# 5-Band_50W_PA_50W_PA_OCP.net
KiCad netlist of a schematic drawn in EAGLE
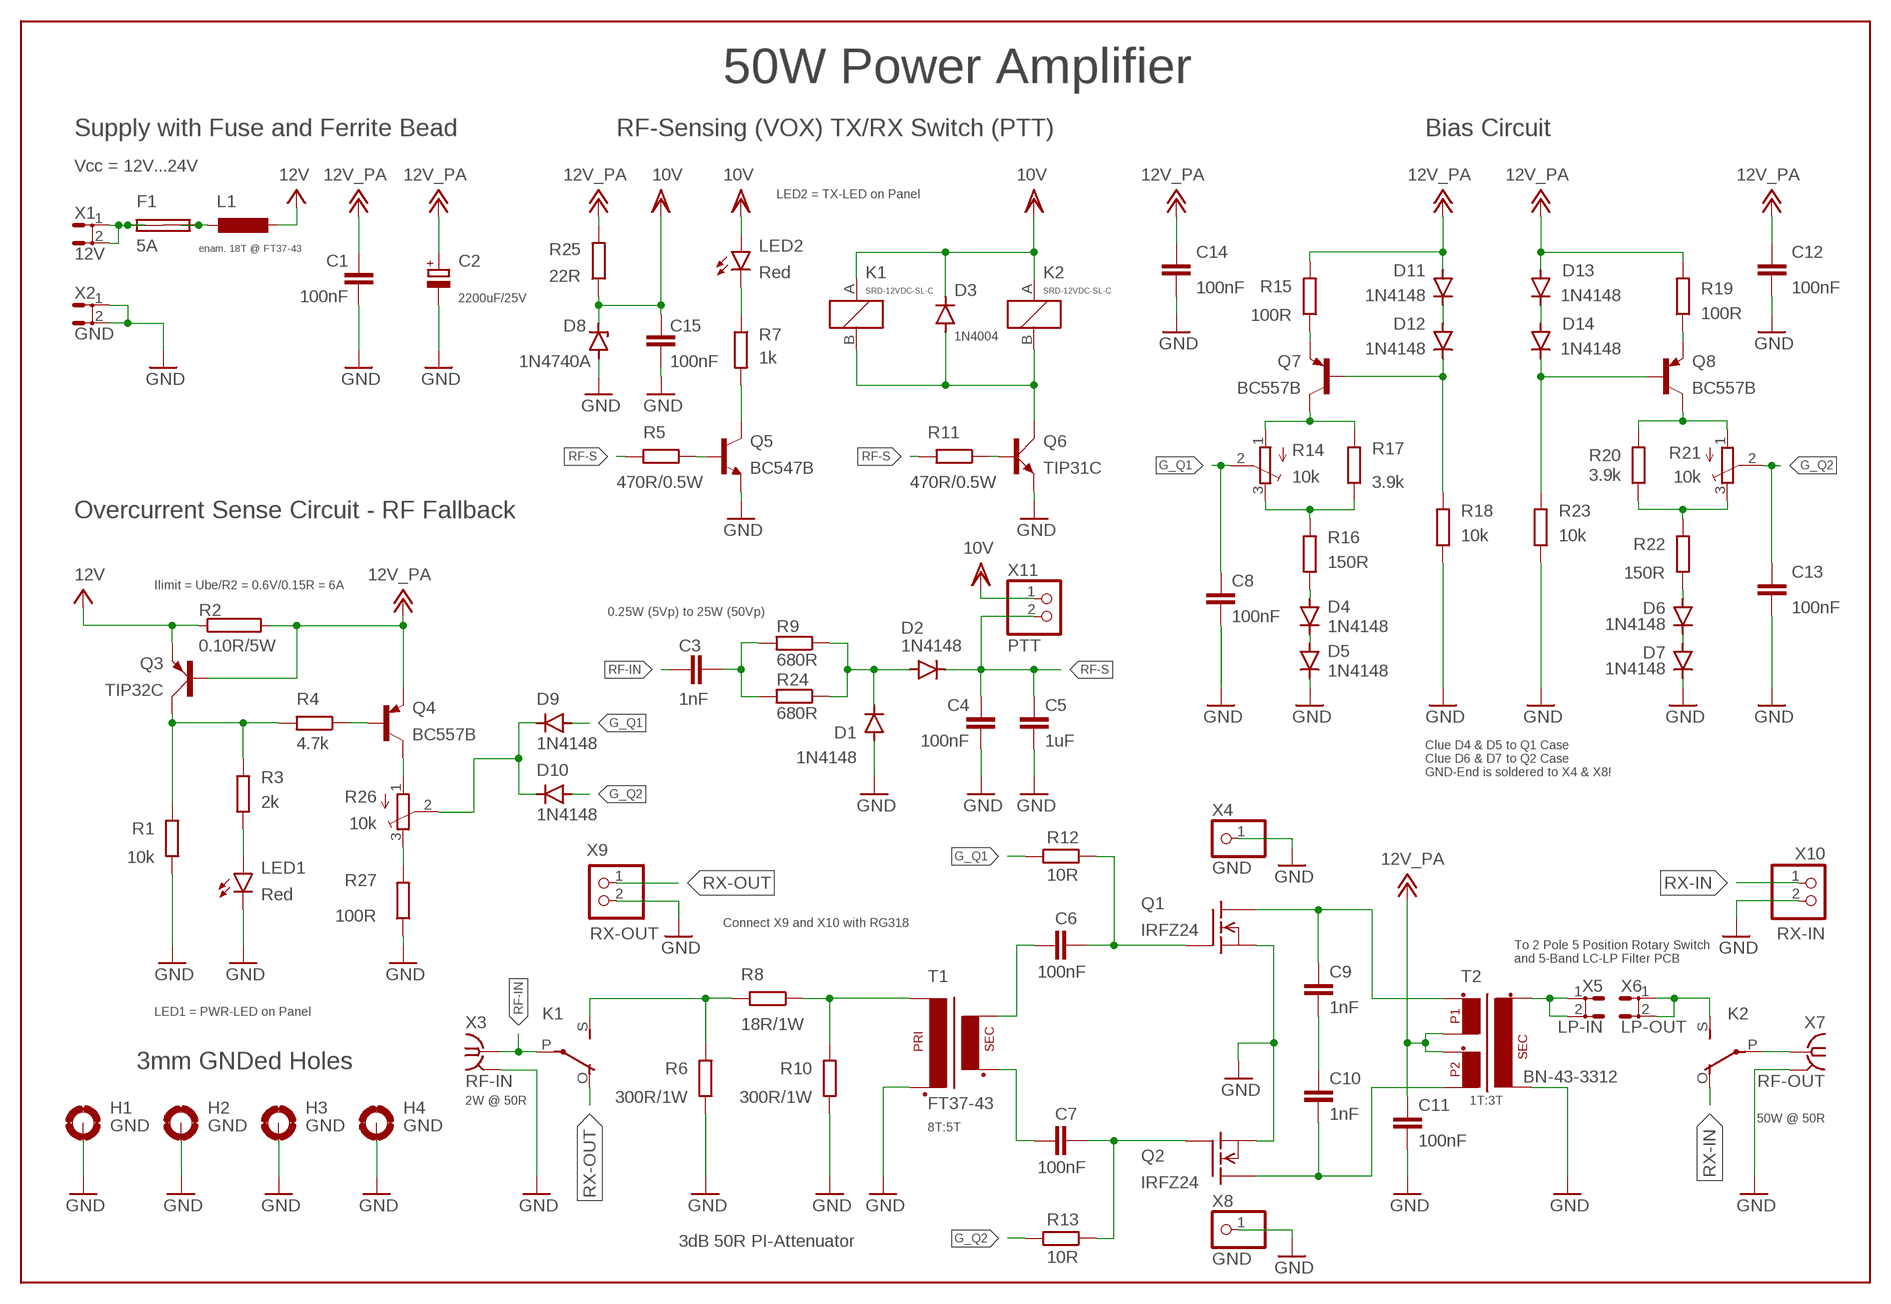
[diagram p0: schematic, sheet 1]

(export (version "E")
  (design (tool "Eeschema 10.0.6"))
  (components
    (comp (ref "C1")
      (value "100nF")
      (footprint "eagle-import:C0805")
      (libsource (lib "eagle-import") (part "C-EUC0805"))
    )
    (comp (ref "C2")
      (value "2200uF/25V")
      (footprint "eagle-import:E7,5-16")
      (libsource (lib "eagle-import") (part "CPOL-EUE7.5-16"))
    )
    (comp (ref "C3")
      (value "1nF")
      (footprint "eagle-import:C0805")
      (libsource (lib "eagle-import") (part "C-EUC0805"))
    )
    (comp (ref "C4")
      (value "100nF")
      (footprint "eagle-import:C0805")
      (libsource (lib "eagle-import") (part "C-EUC0805"))
    )
    (comp (ref "C5")
      (value "1uF")
      (footprint "eagle-import:C0805")
      (libsource (lib "eagle-import") (part "C-EUC0805"))
    )
    (comp (ref "C6")
      (value "100nF")
      (footprint "eagle-import:C0805")
      (libsource (lib "eagle-import") (part "C-EUC0805"))
    )
    (comp (ref "C7")
      (value "100nF")
      (footprint "eagle-import:C0805")
      (libsource (lib "eagle-import") (part "C-EUC0805"))
    )
    (comp (ref "C8")
      (value "100nF")
      (footprint "eagle-import:C0805")
      (libsource (lib "eagle-import") (part "C-EUC0805"))
    )
    (comp (ref "C9")
      (value "1nF")
      (footprint "eagle-import:C1206K")
      (libsource (lib "eagle-import") (part "C-EUC1206K"))
    )
    (comp (ref "C10")
      (value "1nF")
      (footprint "eagle-import:C1206K")
      (libsource (lib "eagle-import") (part "C-EUC1206K"))
    )
    (comp (ref "C11")
      (value "100nF")
      (footprint "eagle-import:C0805")
      (libsource (lib "eagle-import") (part "C-EUC0805"))
    )
    (comp (ref "C12")
      (value "100nF")
      (footprint "eagle-import:C0805")
      (libsource (lib "eagle-import") (part "C-EUC0805"))
    )
    (comp (ref "C13")
      (value "100nF")
      (footprint "eagle-import:C0805")
      (libsource (lib "eagle-import") (part "C-EUC0805"))
    )
    (comp (ref "C14")
      (value "100nF")
      (footprint "eagle-import:C0805")
      (libsource (lib "eagle-import") (part "C-EUC0805"))
    )
    (comp (ref "C15")
      (value "100nF")
      (footprint "eagle-import:C0805")
      (libsource (lib "eagle-import") (part "C-EUC0805"))
    )
    (comp (ref "D1")
      (value "1N4148")
      (footprint "eagle-import:SOD323-W")
      (libsource (lib "eagle-import") (part "DIODE-SOD323-W"))
    )
    (comp (ref "D2")
      (value "1N4148")
      (footprint "eagle-import:SOD323-W")
      (libsource (lib "eagle-import") (part "DIODE-SOD323-W"))
    )
    (comp (ref "D3")
      (value "1N4004")
      (footprint "eagle-import:DO41-10")
      (libsource (lib "eagle-import") (part "1N4004"))
    )
    (comp (ref "D4")
      (value "1N4148")
      (footprint "eagle-import:DO35-7")
      (libsource (lib "eagle-import") (part "1N4148DO35-7"))
    )
    (comp (ref "D5")
      (value "1N4148")
      (footprint "eagle-import:DO35-7")
      (libsource (lib "eagle-import") (part "1N4148DO35-7"))
    )
    (comp (ref "D6")
      (value "1N4148")
      (footprint "eagle-import:DO35-7")
      (libsource (lib "eagle-import") (part "1N4148DO35-7"))
    )
    (comp (ref "D7")
      (value "1N4148")
      (footprint "eagle-import:DO35-7")
      (libsource (lib "eagle-import") (part "1N4148DO35-7"))
    )
    (comp (ref "D8")
      (value "1N4740A")
      (footprint "eagle-import:DO41Z10")
      (libsource (lib "eagle-import") (part "1N4728"))
    )
    (comp (ref "D9")
      (value "1N4148")
      (footprint "eagle-import:SOD323-W")
      (libsource (lib "eagle-import") (part "DIODE-SOD323-W"))
    )
    (comp (ref "D10")
      (value "1N4148")
      (footprint "eagle-import:SOD323-W")
      (libsource (lib "eagle-import") (part "DIODE-SOD323-W"))
    )
    (comp (ref "D11")
      (value "1N4148")
      (footprint "eagle-import:SOD323-W")
      (libsource (lib "eagle-import") (part "DIODE-SOD323-W"))
    )
    (comp (ref "D12")
      (value "1N4148")
      (footprint "eagle-import:SOD323-W")
      (libsource (lib "eagle-import") (part "DIODE-SOD323-W"))
    )
    (comp (ref "D13")
      (value "1N4148")
      (footprint "eagle-import:SOD323-W")
      (libsource (lib "eagle-import") (part "DIODE-SOD323-W"))
    )
    (comp (ref "D14")
      (value "1N4148")
      (footprint "eagle-import:SOD323-W")
      (libsource (lib "eagle-import") (part "DIODE-SOD323-W"))
    )
    (comp (ref "F1")
      (value "5A")
      (footprint "eagle-import:SHK20L")
      (libsource (lib "eagle-import") (part "SHK20L"))
    )
    (comp (ref "H1")
      (value "GND")
      (footprint "eagle-import:3,0-PAD")
      (libsource (lib "eagle-import") (part "MOUNT-PAD-ROUND3.0"))
    )
    (comp (ref "H2")
      (value "GND")
      (footprint "eagle-import:3,0-PAD")
      (libsource (lib "eagle-import") (part "MOUNT-PAD-ROUND3.0"))
    )
    (comp (ref "H3")
      (value "GND")
      (footprint "eagle-import:3,0-PAD")
      (libsource (lib "eagle-import") (part "MOUNT-PAD-ROUND3.0"))
    )
    (comp (ref "H4")
      (value "GND")
      (footprint "eagle-import:3,0-PAD")
      (libsource (lib "eagle-import") (part "MOUNT-PAD-ROUND3.0"))
    )
    (comp (ref "K1")
      (value "SRD-12VDC-SL-C")
      (footprint "eagle-import:SRD-12VDC-SL-C")
      (libsource (lib "eagle-import") (part "SRD-12VDC-SL-C"))
    )
    (comp (ref "K2")
      (value "SRD-12VDC-SL-C")
      (footprint "eagle-import:SRD-12VDC-SL-C")
      (libsource (lib "eagle-import") (part "SRD-12VDC-SL-C"))
    )
    (comp (ref "L1")
      (value "enam. 18T @ FT37-43")
      (footprint "eagle-import:T50-6SMD")
      (libsource (lib "eagle-import") (part "T50-6"))
    )
    (comp (ref "LED1")
      (value "Red")
      (footprint "eagle-import:LED5MM")
      (libsource (lib "eagle-import") (part "LED5MM"))
    )
    (comp (ref "LED2")
      (value "Red")
      (footprint "eagle-import:LED5MM")
      (libsource (lib "eagle-import") (part "LED5MM"))
    )
    (comp (ref "Q1")
      (value "IRFZ24")
      (footprint "eagle-import:TO220")
      (libsource (lib "eagle-import") (part "IRF510"))
    )
    (comp (ref "Q2")
      (value "IRFZ24")
      (footprint "eagle-import:TO220")
      (libsource (lib "eagle-import") (part "IRF510"))
    )
    (comp (ref "Q3")
      (value "TIP32C")
      (footprint "eagle-import:TO220AV")
      (libsource (lib "eagle-import") (part "TIP42C"))
    )
    (comp (ref "Q4")
      (value "BC557B")
      (footprint "eagle-import:TO92-EBC")
      (libsource (lib "eagle-import") (part "BC557B"))
    )
    (comp (ref "Q5")
      (value "BC547B")
      (footprint "eagle-import:TO92-CBE")
      (libsource (lib "eagle-import") (part "-NPN-TO92-CBEBC547B"))
    )
    (comp (ref "Q6")
      (value "TIP31C")
      (footprint "eagle-import:TO220AV")
      (libsource (lib "eagle-import") (part "TIP41C"))
    )
    (comp (ref "Q7")
      (value "BC557B")
      (footprint "eagle-import:TO92-EBC")
      (libsource (lib "eagle-import") (part "BC557B"))
    )
    (comp (ref "Q8")
      (value "BC557B")
      (footprint "eagle-import:TO92-EBC")
      (libsource (lib "eagle-import") (part "BC557B"))
    )
    (comp (ref "R1")
      (value "10k")
      (footprint "eagle-import:R0805")
      (libsource (lib "eagle-import") (part "R-EU_R0805"))
    )
    (comp (ref "R2")
      (value "0.10R/5W")
      (footprint "eagle-import:MNS-5")
      (libsource (lib "eagle-import") (part "RMNS-5"))
    )
    (comp (ref "R3")
      (value "2k")
      (footprint "eagle-import:R0805")
      (libsource (lib "eagle-import") (part "R-EU_R0805"))
    )
    (comp (ref "R4")
      (value "4.7k")
      (footprint "eagle-import:R0805")
      (libsource (lib "eagle-import") (part "R-EU_R0805"))
    )
    (comp (ref "R5")
      (value "470R/0.5W")
      (footprint "eagle-import:0207_10")
      (libsource (lib "eagle-import") (part "R-EU_0207/10"))
    )
    (comp (ref "R6")
      (value "300R/1W")
      (footprint "eagle-import:0414_15")
      (libsource (lib "eagle-import") (part "R-EU_0414/15"))
    )
    (comp (ref "R7")
      (value "1k")
      (footprint "eagle-import:R0805")
      (libsource (lib "eagle-import") (part "R-EU_R0805"))
    )
    (comp (ref "R8")
      (value "18R/1W")
      (footprint "eagle-import:0414_15")
      (libsource (lib "eagle-import") (part "R-EU_0414/15"))
    )
    (comp (ref "R9")
      (value "680R")
      (footprint "eagle-import:R0805")
      (libsource (lib "eagle-import") (part "R-EU_R0805"))
    )
    (comp (ref "R10")
      (value "300R/1W")
      (footprint "eagle-import:0414_15")
      (libsource (lib "eagle-import") (part "R-EU_0414/15"))
    )
    (comp (ref "R11")
      (value "470R/0.5W")
      (footprint "eagle-import:0207_10")
      (libsource (lib "eagle-import") (part "R-EU_0207/10"))
    )
    (comp (ref "R12")
      (value "10R")
      (footprint "eagle-import:0207_10")
      (libsource (lib "eagle-import") (part "R-EU_0207/10"))
    )
    (comp (ref "R13")
      (value "10R")
      (footprint "eagle-import:0207_10")
      (libsource (lib "eagle-import") (part "R-EU_0207/10"))
    )
    (comp (ref "R14")
      (value "10k")
      (footprint "eagle-import:3223G")
      (libsource (lib "eagle-import") (part "TRIM_EU-3223G"))
    )
    (comp (ref "R15")
      (value "100R")
      (footprint "eagle-import:R0805")
      (libsource (lib "eagle-import") (part "R-EU_R0805"))
    )
    (comp (ref "R16")
      (value "150R")
      (footprint "eagle-import:R0805")
      (libsource (lib "eagle-import") (part "R-EU_R0805"))
    )
    (comp (ref "R17")
      (value "3.9k")
      (footprint "eagle-import:R0805")
      (libsource (lib "eagle-import") (part "R-EU_R0805"))
    )
    (comp (ref "R18")
      (value "10k")
      (footprint "eagle-import:R0805")
      (libsource (lib "eagle-import") (part "R-EU_R0805"))
    )
    (comp (ref "R19")
      (value "100R")
      (footprint "eagle-import:R0805")
      (libsource (lib "eagle-import") (part "R-EU_R0805"))
    )
    (comp (ref "R20")
      (value "3.9k")
      (footprint "eagle-import:R0805")
      (libsource (lib "eagle-import") (part "R-EU_R0805"))
    )
    (comp (ref "R21")
      (value "10k")
      (footprint "eagle-import:3223G")
      (libsource (lib "eagle-import") (part "TRIM_EU-3223G"))
    )
    (comp (ref "R22")
      (value "150R")
      (footprint "eagle-import:R0805")
      (libsource (lib "eagle-import") (part "R-EU_R0805"))
    )
    (comp (ref "R23")
      (value "10k")
      (footprint "eagle-import:R0805")
      (libsource (lib "eagle-import") (part "R-EU_R0805"))
    )
    (comp (ref "R24")
      (value "680R")
      (footprint "eagle-import:R0805")
      (libsource (lib "eagle-import") (part "R-EU_R0805"))
    )
    (comp (ref "R25")
      (value "22R")
      (footprint "eagle-import:0207_10")
      (libsource (lib "eagle-import") (part "R-EU_0207/10"))
    )
    (comp (ref "R26")
      (value "10k")
      (footprint "eagle-import:3223G")
      (libsource (lib "eagle-import") (part "TRIM_EU-3223G"))
    )
    (comp (ref "R27")
      (value "100R")
      (footprint "eagle-import:R0805")
      (libsource (lib "eagle-import") (part "R-EU_R0805"))
    )
    (comp (ref "T1")
      (value "FT37-43")
      (footprint "eagle-import:FT37-43SMD")
      (libsource (lib "eagle-import") (part "FT37-43"))
    )
    (comp (ref "T2")
      (value "BN-43-3312")
      (footprint "eagle-import:BN-43-3312CENTERTAPSMD")
      (libsource (lib "eagle-import") (part "BN-43-3312CENTERTAP"))
    )
    (comp (ref "X1")
      (value "12V")
      (footprint "eagle-import:ST6,3")
      (libsource (lib "eagle-import") (part "ST6,3"))
    )
    (comp (ref "X2")
      (value "GND")
      (footprint "eagle-import:ST6,3")
      (libsource (lib "eagle-import") (part "ST6,3"))
    )
    (comp (ref "X3")
      (value "RF-IN")
      (footprint "eagle-import:J502-ND-142-0711-821_826")
      (fields (field (name "MF") "JOHNSON COMPONENTS") (field (name "MPN") "142-0711-821"))
      (libsource (lib "eagle-import") (part "SMA-PCB-CON142-0711-821/826"))
    )
    (comp (ref "X4")
      (value "GND")
      (footprint "eagle-import:1X01")
      (libsource (lib "eagle-import") (part "PINHD-1X1"))
    )
    (comp (ref "X5")
      (value "LP-IN")
      (footprint "eagle-import:ST6,3")
      (libsource (lib "eagle-import") (part "ST6,3"))
    )
    (comp (ref "X6")
      (value "LP-OUT")
      (footprint "eagle-import:ST6,3")
      (libsource (lib "eagle-import") (part "ST6,3"))
    )
    (comp (ref "X7")
      (value "RF-OUT")
      (footprint "eagle-import:J502-ND-142-0711-821_826")
      (fields (field (name "MF") "JOHNSON COMPONENTS") (field (name "MPN") "142-0711-821"))
      (libsource (lib "eagle-import") (part "SMA-PCB-CON142-0711-821/826"))
    )
    (comp (ref "X8")
      (value "GND")
      (footprint "eagle-import:1X01")
      (libsource (lib "eagle-import") (part "PINHD-1X1"))
    )
    (comp (ref "X9")
      (value "RX-OUT")
      (footprint "eagle-import:1X02")
      (libsource (lib "eagle-import") (part "PINHD-1X2"))
    )
    (comp (ref "X10")
      (value "RX-IN")
      (footprint "eagle-import:1X02")
      (libsource (lib "eagle-import") (part "PINHD-1X2"))
    )
    (comp (ref "X11")
      (value "PTT")
      (footprint "eagle-import:1X02")
      (libsource (lib "eagle-import") (part "PINHD-1X2"))
    )
  )
  (nets
    (net (code "1") (name "10V") (class "Default")
      (node (ref "C15") (pin "2") (pinfunction "2_2") (pintype "passive"))
      (node (ref "D3") (pin "C") (pinfunction "C_C") (pintype "passive"))
      (node (ref "D8") (pin "C") (pinfunction "C_C") (pintype "passive"))
      (node (ref "K1") (pin "A") (pinfunction "A_A") (pintype "passive"))
      (node (ref "K2") (pin "A") (pinfunction "A_A") (pintype "passive"))
      (node (ref "LED2") (pin "A") (pinfunction "A_A") (pintype "passive"))
      (node (ref "R25") (pin "1") (pinfunction "1_1") (pintype "passive"))
      (node (ref "X11") (pin "1") (pinfunction "1_1") (pintype "passive"))
    )
    (net (code "2") (name "12V") (class "Default")
      (node (ref "L1") (pin "P$2") (pinfunction "2_P$2") (pintype "passive"))
      (node (ref "Q3") (pin "E") (pinfunction "E_E") (pintype "passive"))
      (node (ref "R2") (pin "1") (pinfunction "1_1") (pintype "passive"))
    )
    (net (code "3") (name "12V_PA") (class "Default")
      (node (ref "C1") (pin "2") (pinfunction "2_2") (pintype "passive"))
      (node (ref "C11") (pin "2") (pinfunction "2_2") (pintype "passive"))
      (node (ref "C12") (pin "2") (pinfunction "2_2") (pintype "passive"))
      (node (ref "C14") (pin "2") (pinfunction "2_2") (pintype "passive"))
      (node (ref "C2") (pin "+") (pinfunction "+_+") (pintype "passive"))
      (node (ref "D11") (pin "A") (pinfunction "A_A") (pintype "passive"))
      (node (ref "D13") (pin "A") (pinfunction "A_A") (pintype "passive"))
      (node (ref "Q3") (pin "B") (pinfunction "B_B") (pintype "passive"))
      (node (ref "Q4") (pin "E") (pinfunction "E_E") (pintype "passive"))
      (node (ref "R15") (pin "2") (pinfunction "2_2") (pintype "passive"))
      (node (ref "R19") (pin "2") (pinfunction "2_2") (pintype "passive"))
      (node (ref "R2") (pin "2") (pinfunction "2_2") (pintype "passive"))
      (node (ref "R25") (pin "2") (pinfunction "2_2") (pintype "passive"))
      (node (ref "T2") (pin "P$2") (pinfunction "P1_2_P$2") (pintype "passive"))
      (node (ref "T2") (pin "P$3") (pinfunction "P2_1_P$3") (pintype "passive"))
    )
    (net (code "4") (name "GND") (class "Default")
      (node (ref "C1") (pin "1") (pinfunction "1_1") (pintype "passive"))
      (node (ref "C11") (pin "1") (pinfunction "1_1") (pintype "passive"))
      (node (ref "C12") (pin "1") (pinfunction "1_1") (pintype "passive"))
      (node (ref "C13") (pin "1") (pinfunction "1_1") (pintype "passive"))
      (node (ref "C14") (pin "1") (pinfunction "1_1") (pintype "passive"))
      (node (ref "C15") (pin "1") (pinfunction "1_1") (pintype "passive"))
      (node (ref "C2") (pin "-") (pinfunction "-_-") (pintype "passive"))
      (node (ref "C4") (pin "1") (pinfunction "1_1") (pintype "passive"))
      (node (ref "C5") (pin "1") (pinfunction "1_1") (pintype "passive"))
      (node (ref "C8") (pin "1") (pinfunction "1_1") (pintype "passive"))
      (node (ref "D1") (pin "A") (pinfunction "A_A") (pintype "passive"))
      (node (ref "D5") (pin "C") (pinfunction "C_C") (pintype "passive"))
      (node (ref "D7") (pin "C") (pinfunction "C_C") (pintype "passive"))
      (node (ref "D8") (pin "A") (pinfunction "A_A") (pintype "passive"))
      (node (ref "H1") (pin "B3,0") (pinfunction "MOUNT_B3,0") (pintype "passive"))
      (node (ref "H2") (pin "B3,0") (pinfunction "MOUNT_B3,0") (pintype "passive"))
      (node (ref "H3") (pin "B3,0") (pinfunction "MOUNT_B3,0") (pintype "passive"))
      (node (ref "H4") (pin "B3,0") (pinfunction "MOUNT_B3,0") (pintype "passive"))
      (node (ref "LED1") (pin "K") (pinfunction "C_K") (pintype "passive"))
      (node (ref "Q1") (pin "3") (pinfunction "S_3") (pintype "passive"))
      (node (ref "Q2") (pin "3") (pinfunction "S_3") (pintype "passive"))
      (node (ref "Q5") (pin "E") (pinfunction "E_E") (pintype "passive"))
      (node (ref "Q6") (pin "E") (pinfunction "E_E") (pintype "passive"))
      (node (ref "R1") (pin "1") (pinfunction "1_1") (pintype "passive"))
      (node (ref "R10") (pin "1") (pinfunction "1_1") (pintype "passive"))
      (node (ref "R18") (pin "1") (pinfunction "1_1") (pintype "passive"))
      (node (ref "R23") (pin "1") (pinfunction "1_1") (pintype "passive"))
      (node (ref "R27") (pin "1") (pinfunction "1_1") (pintype "passive"))
      (node (ref "R6") (pin "1") (pinfunction "1_1") (pintype "passive"))
      (node (ref "T1") (pin "P$2") (pinfunction "P2_P$2") (pintype "passive"))
      (node (ref "T2") (pin "S$2") (pinfunction "S2_S$2") (pintype "passive"))
      (node (ref "X10") (pin "2") (pinfunction "2_2") (pintype "passive"))
      (node (ref "X2") (pin "1") (pinfunction "1_1") (pintype "passive"))
      (node (ref "X2") (pin "2") (pinfunction "2_2") (pintype "passive"))
      (node (ref "X3") (pin "G@1") (pinfunction "GND_G@1") (pintype "passive"))
      (node (ref "X3") (pin "G@2") (pinfunction "GND_G@2") (pintype "passive"))
      (node (ref "X3") (pin "G@3") (pinfunction "GND_G@3") (pintype "passive"))
      (node (ref "X3") (pin "G@4") (pinfunction "GND_G@4") (pintype "passive"))
      (node (ref "X4") (pin "1") (pinfunction "1_1") (pintype "passive"))
      (node (ref "X7") (pin "G@1") (pinfunction "GND_G@1") (pintype "passive"))
      (node (ref "X7") (pin "G@2") (pinfunction "GND_G@2") (pintype "passive"))
      (node (ref "X7") (pin "G@3") (pinfunction "GND_G@3") (pintype "passive"))
      (node (ref "X7") (pin "G@4") (pinfunction "GND_G@4") (pintype "passive"))
      (node (ref "X8") (pin "1") (pinfunction "1_1") (pintype "passive"))
      (node (ref "X9") (pin "2") (pinfunction "2_2") (pintype "passive"))
    )
    (net (code "5") (name "G_Q1") (class "Default")
      (node (ref "C8") (pin "2") (pinfunction "2_2") (pintype "passive"))
      (node (ref "D9") (pin "A") (pinfunction "A_A") (pintype "passive"))
      (node (ref "R12") (pin "2") (pinfunction "2_2") (pintype "passive"))
      (node (ref "R14") (pin "2") (pinfunction "S_2") (pintype "passive"))
    )
    (net (code "6") (name "G_Q2") (class "Default")
      (node (ref "C13") (pin "2") (pinfunction "2_2") (pintype "passive"))
      (node (ref "D10") (pin "A") (pinfunction "A_A") (pintype "passive"))
      (node (ref "R13") (pin "2") (pinfunction "2_2") (pintype "passive"))
      (node (ref "R21") (pin "2") (pinfunction "S_2") (pintype "passive"))
    )
    (net (code "7") (name "Net-(C3-Pad1)") (class "Default")
      (node (ref "C3") (pin "1") (pinfunction "1_1") (pintype "passive"))
      (node (ref "R24") (pin "2") (pinfunction "2_2") (pintype "passive"))
      (node (ref "R9") (pin "2") (pinfunction "2_2") (pintype "passive"))
    )
    (net (code "8") (name "Net-(C10-Pad1)") (class "Default")
      (node (ref "C10") (pin "1") (pinfunction "1_1") (pintype "passive"))
      (node (ref "C9") (pin "2") (pinfunction "2_2") (pintype "passive"))
    )
    (net (code "9") (name "Net-(D1-PadC)") (class "Default")
      (node (ref "D1") (pin "C") (pinfunction "C_C") (pintype "passive"))
      (node (ref "D2") (pin "A") (pinfunction "A_A") (pintype "passive"))
      (node (ref "R24") (pin "1") (pinfunction "1_1") (pintype "passive"))
      (node (ref "R9") (pin "1") (pinfunction "1_1") (pintype "passive"))
    )
    (net (code "10") (name "Net-(D3-PadA)") (class "Default")
      (node (ref "D3") (pin "A") (pinfunction "A_A") (pintype "passive"))
      (node (ref "K1") (pin "B") (pinfunction "B_B") (pintype "passive"))
      (node (ref "K2") (pin "B") (pinfunction "B_B") (pintype "passive"))
      (node (ref "Q6") (pin "C") (pinfunction "C_C") (pintype "passive"))
    )
    (net (code "11") (name "Net-(D4-PadA)") (class "Default")
      (node (ref "D4") (pin "A") (pinfunction "A_A") (pintype "passive"))
      (node (ref "R16") (pin "1") (pinfunction "1_1") (pintype "passive"))
    )
    (net (code "12") (name "Net-(D4-PadC)") (class "Default")
      (node (ref "D4") (pin "C") (pinfunction "C_C") (pintype "passive"))
      (node (ref "D5") (pin "A") (pinfunction "A_A") (pintype "passive"))
    )
    (net (code "13") (name "Net-(D6-PadA)") (class "Default")
      (node (ref "D6") (pin "A") (pinfunction "A_A") (pintype "passive"))
      (node (ref "R22") (pin "1") (pinfunction "1_1") (pintype "passive"))
    )
    (net (code "14") (name "Net-(D6-PadC)") (class "Default")
      (node (ref "D6") (pin "C") (pinfunction "C_C") (pintype "passive"))
      (node (ref "D7") (pin "A") (pinfunction "A_A") (pintype "passive"))
    )
    (net (code "15") (name "Net-(D11-PadC)") (class "Default")
      (node (ref "D11") (pin "C") (pinfunction "C_C") (pintype "passive"))
      (node (ref "D12") (pin "A") (pinfunction "A_A") (pintype "passive"))
    )
    (net (code "16") (name "Net-(D12-PadC)") (class "Default")
      (node (ref "D12") (pin "C") (pinfunction "C_C") (pintype "passive"))
      (node (ref "Q7") (pin "B") (pinfunction "B_B") (pintype "passive"))
      (node (ref "R18") (pin "2") (pinfunction "2_2") (pintype "passive"))
    )
    (net (code "17") (name "Net-(D13-PadC)") (class "Default")
      (node (ref "D13") (pin "C") (pinfunction "C_C") (pintype "passive"))
      (node (ref "D14") (pin "A") (pinfunction "A_A") (pintype "passive"))
    )
    (net (code "18") (name "Net-(D14-PadC)") (class "Default")
      (node (ref "D14") (pin "C") (pinfunction "C_C") (pintype "passive"))
      (node (ref "Q8") (pin "B") (pinfunction "B_B") (pintype "passive"))
      (node (ref "R23") (pin "2") (pinfunction "2_2") (pintype "passive"))
    )
    (net (code "19") (name "Net-(F1-Pad1A)") (class "Default")
      (node (ref "F1") (pin "1A") (pinfunction "1A_1A") (pintype "passive"))
      (node (ref "F1") (pin "1B") (pinfunction "1B_1B") (pintype "passive"))
      (node (ref "X1") (pin "1") (pinfunction "1_1") (pintype "passive"))
      (node (ref "X1") (pin "2") (pinfunction "2_2") (pintype "passive"))
    )
    (net (code "20") (name "Net-(K1-PadS)") (class "Default")
      (node (ref "K1") (pin "S") (pinfunction "S_S") (pintype "passive"))
      (node (ref "R6") (pin "2") (pinfunction "2_2") (pintype "passive"))
      (node (ref "R8") (pin "2") (pinfunction "2_2") (pintype "passive"))
    )
    (net (code "21") (name "Net-(K2-PadS)") (class "Default")
      (node (ref "K2") (pin "S") (pinfunction "S_S") (pintype "passive"))
      (node (ref "X6") (pin "1") (pinfunction "1_1") (pintype "passive"))
      (node (ref "X6") (pin "2") (pinfunction "2_2") (pintype "passive"))
    )
    (net (code "22") (name "Net-(L1-1)") (class "Default")
      (node (ref "F1") (pin "2A") (pinfunction "2A_2A") (pintype "passive"))
      (node (ref "F1") (pin "2B") (pinfunction "2B_2B") (pintype "passive"))
      (node (ref "L1") (pin "P$1") (pinfunction "1_P$1") (pintype "passive"))
    )
    (net (code "23") (name "Net-(LED1-PadA)") (class "Default")
      (node (ref "LED1") (pin "A") (pinfunction "A_A") (pintype "passive"))
      (node (ref "R3") (pin "1") (pinfunction "1_1") (pintype "passive"))
    )
    (net (code "24") (name "Net-(LED2-C)") (class "Default")
      (node (ref "LED2") (pin "K") (pinfunction "C_K") (pintype "passive"))
      (node (ref "R7") (pin "1") (pinfunction "1_1") (pintype "passive"))
    )
    (net (code "25") (name "Net-(Q1-D)") (class "Default")
      (node (ref "C9") (pin "1") (pinfunction "1_1") (pintype "passive"))
      (node (ref "Q1") (pin "2") (pinfunction "D_2") (pintype "passive"))
      (node (ref "T2") (pin "P$1") (pinfunction "P1_1_P$1") (pintype "passive"))
    )
    (net (code "26") (name "Net-(Q1-G)") (class "Default")
      (node (ref "C6") (pin "1") (pinfunction "1_1") (pintype "passive"))
      (node (ref "Q1") (pin "1") (pinfunction "G_1") (pintype "passive"))
      (node (ref "R12") (pin "1") (pinfunction "1_1") (pintype "passive"))
    )
    (net (code "27") (name "Net-(Q2-D)") (class "Default")
      (node (ref "C10") (pin "2") (pinfunction "2_2") (pintype "passive"))
      (node (ref "Q2") (pin "2") (pinfunction "D_2") (pintype "passive"))
      (node (ref "T2") (pin "P$4") (pinfunction "P2_2_P$4") (pintype "passive"))
    )
    (net (code "28") (name "Net-(Q2-G)") (class "Default")
      (node (ref "C7") (pin "1") (pinfunction "1_1") (pintype "passive"))
      (node (ref "Q2") (pin "1") (pinfunction "G_1") (pintype "passive"))
      (node (ref "R13") (pin "1") (pinfunction "1_1") (pintype "passive"))
    )
    (net (code "29") (name "Net-(Q3-PadC)") (class "Default")
      (node (ref "Q3") (pin "C") (pinfunction "C_C") (pintype "passive"))
      (node (ref "R1") (pin "2") (pinfunction "2_2") (pintype "passive"))
      (node (ref "R3") (pin "2") (pinfunction "2_2") (pintype "passive"))
      (node (ref "R4") (pin "2") (pinfunction "2_2") (pintype "passive"))
    )
    (net (code "30") (name "Net-(Q4-PadB)") (class "Default")
      (node (ref "Q4") (pin "B") (pinfunction "B_B") (pintype "passive"))
      (node (ref "R4") (pin "1") (pinfunction "1_1") (pintype "passive"))
    )
    (net (code "31") (name "Net-(Q5-PadB)") (class "Default")
      (node (ref "Q5") (pin "B") (pinfunction "B_B") (pintype "passive"))
      (node (ref "R5") (pin "1") (pinfunction "1_1") (pintype "passive"))
    )
    (net (code "32") (name "Net-(Q5-PadC)") (class "Default")
      (node (ref "Q5") (pin "C") (pinfunction "C_C") (pintype "passive"))
      (node (ref "R7") (pin "2") (pinfunction "2_2") (pintype "passive"))
    )
    (net (code "33") (name "Net-(Q6-PadB)") (class "Default")
      (node (ref "Q6") (pin "B") (pinfunction "B_B") (pintype "passive"))
      (node (ref "R11") (pin "1") (pinfunction "1_1") (pintype "passive"))
    )
    (net (code "34") (name "Net-(Q7-PadE)") (class "Default")
      (node (ref "Q7") (pin "E") (pinfunction "E_E") (pintype "passive"))
      (node (ref "R15") (pin "1") (pinfunction "1_1") (pintype "passive"))
    )
    (net (code "35") (name "Net-(Q8-PadE)") (class "Default")
      (node (ref "Q8") (pin "E") (pinfunction "E_E") (pintype "passive"))
      (node (ref "R19") (pin "1") (pinfunction "1_1") (pintype "passive"))
    )
    (net (code "36") (name "Net-(R14-A)") (class "Default")
      (node (ref "Q7") (pin "C") (pinfunction "C_C") (pintype "passive"))
      (node (ref "R14") (pin "1") (pinfunction "A_1") (pintype "passive"))
      (node (ref "R17") (pin "2") (pinfunction "2_2") (pintype "passive"))
    )
    (net (code "37") (name "Net-(R14-E)") (class "Default")
      (node (ref "R14") (pin "3") (pinfunction "E_3") (pintype "passive"))
      (node (ref "R16") (pin "2") (pinfunction "2_2") (pintype "passive"))
      (node (ref "R17") (pin "1") (pinfunction "1_1") (pintype "passive"))
    )
    (net (code "38") (name "Net-(R21-A)") (class "Default")
      (node (ref "Q8") (pin "C") (pinfunction "C_C") (pintype "passive"))
      (node (ref "R20") (pin "2") (pinfunction "2_2") (pintype "passive"))
      (node (ref "R21") (pin "1") (pinfunction "A_1") (pintype "passive"))
    )
    (net (code "39") (name "Net-(R21-E)") (class "Default")
      (node (ref "R20") (pin "1") (pinfunction "1_1") (pintype "passive"))
      (node (ref "R21") (pin "3") (pinfunction "E_3") (pintype "passive"))
      (node (ref "R22") (pin "2") (pinfunction "2_2") (pintype "passive"))
    )
    (net (code "40") (name "Net-(R26-A)") (class "Default")
      (node (ref "Q4") (pin "C") (pinfunction "C_C") (pintype "passive"))
      (node (ref "R26") (pin "1") (pinfunction "A_1") (pintype "passive"))
    )
    (net (code "41") (name "Net-(R26-E)") (class "Default")
      (node (ref "R26") (pin "3") (pinfunction "E_3") (pintype "passive"))
      (node (ref "R27") (pin "2") (pinfunction "2_2") (pintype "passive"))
    )
    (net (code "42") (name "Net-(R26-S)") (class "Default")
      (node (ref "D10") (pin "C") (pinfunction "C_C") (pintype "passive"))
      (node (ref "D9") (pin "C") (pinfunction "C_C") (pintype "passive"))
      (node (ref "R26") (pin "2") (pinfunction "S_2") (pintype "passive"))
    )
    (net (code "43") (name "Net-(T1-P1)") (class "Default")
      (node (ref "R10") (pin "2") (pinfunction "2_2") (pintype "passive"))
      (node (ref "R8") (pin "1") (pinfunction "1_1") (pintype "passive"))
      (node (ref "T1") (pin "P$1") (pinfunction "P1_P$1") (pintype "passive"))
    )
    (net (code "44") (name "Net-(T1-S1)") (class "Default")
      (node (ref "C6") (pin "2") (pinfunction "2_2") (pintype "passive"))
      (node (ref "T1") (pin "S$1") (pinfunction "S1_S$1") (pintype "passive"))
    )
    (net (code "45") (name "Net-(T1-S2)") (class "Default")
      (node (ref "C7") (pin "2") (pinfunction "2_2") (pintype "passive"))
      (node (ref "T1") (pin "S$2") (pinfunction "S2_S$2") (pintype "passive"))
    )
    (net (code "46") (name "Net-(T2-S1)") (class "Default")
      (node (ref "T2") (pin "S$1") (pinfunction "S1_S$1") (pintype "passive"))
      (node (ref "X5") (pin "1") (pinfunction "1_1") (pintype "passive"))
      (node (ref "X5") (pin "2") (pinfunction "2_2") (pintype "passive"))
    )
    (net (code "47") (name "Net-(X7-RF)") (class "Default")
      (node (ref "K2") (pin "P") (pinfunction "P_P") (pintype "passive"))
      (node (ref "X7") (pin "1") (pinfunction "RF_1") (pintype "passive"))
    )
    (net (code "48") (name "RF-IN") (class "Default")
      (node (ref "C3") (pin "2") (pinfunction "2_2") (pintype "passive"))
      (node (ref "K1") (pin "P") (pinfunction "P_P") (pintype "passive"))
      (node (ref "X3") (pin "1") (pinfunction "RF_1") (pintype "passive"))
    )
    (net (code "49") (name "RF-S") (class "Default")
      (node (ref "C4") (pin "2") (pinfunction "2_2") (pintype "passive"))
      (node (ref "C5") (pin "2") (pinfunction "2_2") (pintype "passive"))
      (node (ref "D2") (pin "C") (pinfunction "C_C") (pintype "passive"))
      (node (ref "R11") (pin "2") (pinfunction "2_2") (pintype "passive"))
      (node (ref "R5") (pin "2") (pinfunction "2_2") (pintype "passive"))
      (node (ref "X11") (pin "2") (pinfunction "2_2") (pintype "passive"))
    )
    (net (code "50") (name "RX-IN") (class "Default")
      (node (ref "K2") (pin "O") (pinfunction "O_O") (pintype "passive"))
      (node (ref "X10") (pin "1") (pinfunction "1_1") (pintype "passive"))
    )
    (net (code "51") (name "RX-OUT") (class "Default")
      (node (ref "K1") (pin "O") (pinfunction "O_O") (pintype "passive"))
      (node (ref "X9") (pin "1") (pinfunction "1_1") (pintype "passive"))
    )
  )
)
